# Energino.net
KiCad netlist of a schematic drawn in Altium Designer
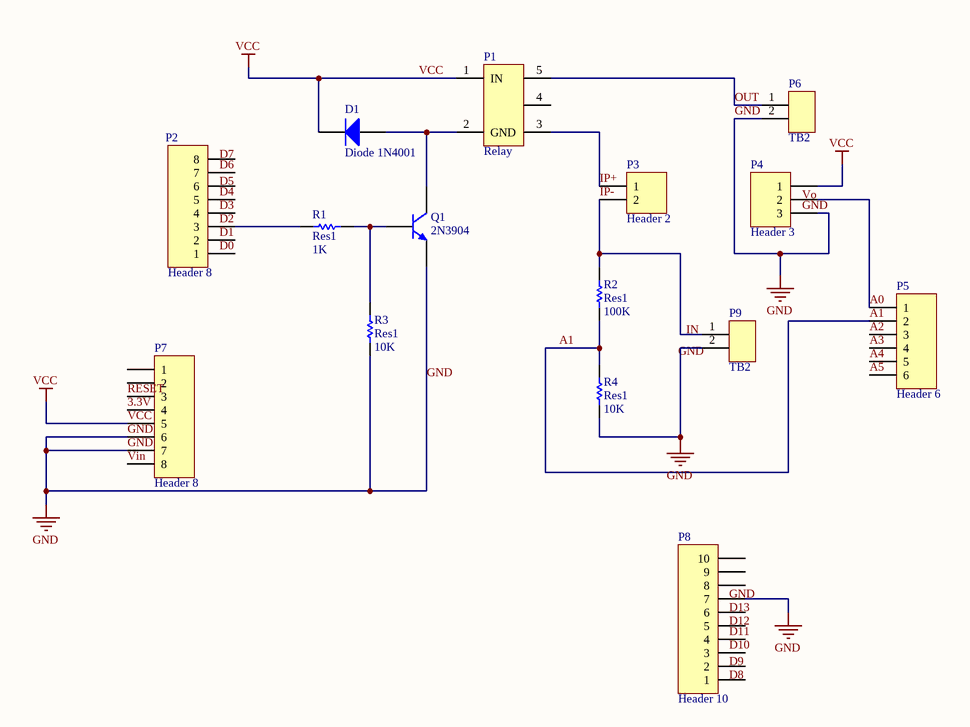
[diagram p0: Energino.SchDoc]

(export (version "E")
  (design (tool "Eeschema 10.0.6"))
  (components
    (comp (ref "D1")
      (value "Diode 1N4001")
      (footprint "DO-41")
      (description "1 Amp General Purpose Rectifier")
      (fields (field (name "PUBLISHER") "Altium Limited"))
      (libsource (lib "Miscellaneous Devices") (part "Diode 1N4001"))
    )
    (comp (ref "P1") (value "Relay") (footprint "JQC-3F") (libsource (lib "Winton") (part "JQC-3F")))
    (comp (ref "P2")
      (value "Header 8")
      (footprint "HDR1X8")
      (description "Header, 8-Pin")
      (fields (field (name "PUBLISHER") "Altium Limited"))
      (libsource (lib "") (part "Header 8_1"))
    )
    (comp (ref "P3")
      (value "Header 2")
      (footprint "HDR1X2")
      (description "Header, 2-Pin")
      (fields (field (name "PUBLISHER") "Altium Limited"))
      (libsource (lib "Miscellaneous Connectors") (part "Header 2"))
    )
    (comp (ref "P4")
      (value "Header 3")
      (footprint "HDR1X3")
      (description "Header, 3-Pin")
      (fields (field (name "PUBLISHER") "Altium Limited"))
      (libsource (lib "Miscellaneous Connectors") (part "Header 3"))
    )
    (comp (ref "P5")
      (value "Header 6")
      (footprint "HDR1X6")
      (description "Header, 6-Pin")
      (fields (field (name "PUBLISHER") "Altium Limited"))
      (libsource (lib "Miscellaneous Connectors") (part "Header 6"))
    )
    (comp (ref "P6") (value "TB2") (footprint "TB2") (libsource (lib "Winton") (part "TB2")))
    (comp (ref "P7")
      (value "Header 8")
      (footprint "HDR1X8")
      (description "Header, 8-Pin")
      (fields (field (name "PUBLISHER") "Altium Limited"))
      (libsource (lib "Miscellaneous Connectors") (part "Header 8"))
    )
    (comp (ref "P8")
      (value "Header 10")
      (footprint "HDR1X10")
      (description "Header, 10-Pin")
      (fields (field (name "PUBLISHER") "Altium Limited"))
      (libsource (lib "Miscellaneous Connectors") (part "Header 10"))
    )
    (comp (ref "P9") (value "TB2") (footprint "TB2") (libsource (lib "Winton") (part "TB2")))
    (comp (ref "Q1")
      (value "2N3904")
      (footprint "TO-92A")
      (description "NPN General Purpose Amplifier")
      (fields (field (name "PUBLISHER") "Altium Limited"))
      (libsource (lib "Miscellaneous Devices") (part "2N3904"))
    )
    (comp (ref "R1")
      (value "Res1")
      (footprint "AXIAL-0.3")
      (description "Resistor")
      (fields (field (name "ALTIUM_VALUE") "1K") (field (name "PUBLISHER") "Altium Limited"))
      (libsource (lib "Miscellaneous Devices") (part "Res1"))
    )
    (comp (ref "R2")
      (value "Res1")
      (footprint "AXIAL-0.3")
      (description "Resistor")
      (fields (field (name "ALTIUM_VALUE") "100K") (field (name "PUBLISHER") "Altium Limited"))
      (libsource (lib "Miscellaneous Devices") (part "Res1"))
    )
    (comp (ref "R3")
      (value "Res1")
      (footprint "AXIAL-0.3")
      (description "Resistor")
      (fields (field (name "ALTIUM_VALUE") "10K") (field (name "PUBLISHER") "Altium Limited"))
      (libsource (lib "Miscellaneous Devices") (part "Res1"))
    )
    (comp (ref "R4")
      (value "Res1")
      (footprint "AXIAL-0.3")
      (description "Resistor")
      (fields (field (name "ALTIUM_VALUE") "10K") (field (name "PUBLISHER") "Altium Limited"))
      (libsource (lib "Miscellaneous Devices") (part "Res1"))
    )
  )
  (nets
    (net (code "1") (name "/3.3V") (class "Default")
      (node (ref "P7") (pin "4") (pinfunction "4_4") (pintype "passive"))
    )
    (net (code "2") (name "/A0") (class "Default")
      (node (ref "P4") (pin "2") (pinfunction "2_2") (pintype "passive"))
      (node (ref "P5") (pin "1") (pinfunction "1_1") (pintype "passive"))
    )
    (net (code "3") (name "/A1") (class "Default")
      (node (ref "P5") (pin "2") (pinfunction "2_2") (pintype "passive"))
      (node (ref "R2") (pin "1") (pinfunction "1_1") (pintype "passive"))
      (node (ref "R4") (pin "2") (pinfunction "2_2") (pintype "passive"))
    )
    (net (code "4") (name "/A2") (class "Default")
      (node (ref "P5") (pin "3") (pinfunction "3_3") (pintype "passive"))
    )
    (net (code "5") (name "/A3") (class "Default")
      (node (ref "P5") (pin "4") (pinfunction "4_4") (pintype "passive"))
    )
    (net (code "6") (name "/A4") (class "Default")
      (node (ref "P5") (pin "5") (pinfunction "5_5") (pintype "passive"))
    )
    (net (code "7") (name "/A5") (class "Default")
      (node (ref "P5") (pin "6") (pinfunction "6_6") (pintype "passive"))
    )
    (net (code "23") (name "/IP+") (class "Default")
      (node (ref "P1") (pin "3") (pinfunction "3_3") (pintype "passive"))
      (node (ref "P3") (pin "1") (pinfunction "1_1") (pintype "passive"))
    )
    (net (code "24") (name "/IP-") (class "Default")
      (node (ref "P3") (pin "2") (pinfunction "2_2") (pintype "passive"))
      (node (ref "P9") (pin "1") (pinfunction "1_1") (pintype "passive"))
      (node (ref "R2") (pin "2") (pinfunction "2_2") (pintype "passive"))
    )
    (net (code "25") (name "/OUT") (class "Default")
      (node (ref "P1") (pin "5") (pinfunction "5_5") (pintype "passive"))
      (node (ref "P6") (pin "1") (pinfunction "1_1") (pintype "passive"))
    )
    (net (code "26") (name "/RESET") (class "Default")
      (node (ref "P7") (pin "3") (pinfunction "3_3") (pintype "passive"))
    )
    (net (code "27") (name "/Vin") (class "Default")
      (node (ref "P7") (pin "8") (pinfunction "8_8") (pintype "passive"))
    )
    (net (code "29") (name "GND") (class "Default")
      (node (ref "P4") (pin "3") (pinfunction "3_3") (pintype "passive"))
      (node (ref "P6") (pin "2") (pinfunction "2_2") (pintype "passive"))
      (node (ref "P7") (pin "6") (pinfunction "6_6") (pintype "passive"))
      (node (ref "P7") (pin "7") (pinfunction "7_7") (pintype "passive"))
      (node (ref "P8") (pin "7") (pinfunction "7_7") (pintype "passive"))
      (node (ref "P9") (pin "2") (pinfunction "2_2") (pintype "passive"))
      (node (ref "Q1") (pin "1") (pinfunction "E_1") (pintype "passive"))
      (node (ref "R3") (pin "1") (pinfunction "1_1") (pintype "passive"))
      (node (ref "R4") (pin "1") (pinfunction "1_1") (pintype "passive"))
    )
    (net (code "30") (name "Net-(D1-A)") (class "Default")
      (node (ref "D1") (pin "1") (pinfunction "A_1") (pintype "passive"))
      (node (ref "P1") (pin "2") (pinfunction "GND_2") (pintype "passive"))
      (node (ref "Q1") (pin "3") (pinfunction "C_3") (pintype "passive"))
    )
    (net (code "31") (name "Net-(P2-Pad3)") (class "Default")
      (node (ref "P2") (pin "3") (pinfunction "3_3") (pintype "passive"))
      (node (ref "R1") (pin "1") (pinfunction "1_1") (pintype "passive"))
    )
    (net (code "32") (name "Net-(Q1-B)") (class "Default")
      (node (ref "Q1") (pin "2") (pinfunction "B_2") (pintype "passive"))
      (node (ref "R1") (pin "2") (pinfunction "2_2") (pintype "passive"))
      (node (ref "R3") (pin "2") (pinfunction "2_2") (pintype "passive"))
    )
    (net (code "33") (name "VCC") (class "Default")
      (node (ref "D1") (pin "2") (pinfunction "K_2") (pintype "passive"))
      (node (ref "P1") (pin "1") (pinfunction "IN_1") (pintype "passive"))
      (node (ref "P4") (pin "1") (pinfunction "1_1") (pintype "passive"))
      (node (ref "P7") (pin "5") (pinfunction "5_5") (pintype "passive"))
    )
    (net (code "34") (name "unconnected-(P1-Pad4)") (class "Default")
      (node (ref "P1") (pin "4") (pinfunction "4_4") (pintype "passive"))
    )
    (net (code "35") (name "unconnected-(P2-Pad1)") (class "Default")
      (node (ref "P2") (pin "1") (pinfunction "1_1") (pintype "passive"))
    )
    (net (code "36") (name "unconnected-(P2-Pad2)") (class "Default")
      (node (ref "P2") (pin "2") (pinfunction "2_2") (pintype "passive"))
    )
    (net (code "37") (name "unconnected-(P2-Pad4)") (class "Default")
      (node (ref "P2") (pin "4") (pinfunction "4_4") (pintype "passive"))
    )
    (net (code "38") (name "unconnected-(P2-Pad5)") (class "Default")
      (node (ref "P2") (pin "5") (pinfunction "5_5") (pintype "passive"))
    )
    (net (code "39") (name "unconnected-(P2-Pad6)") (class "Default")
      (node (ref "P2") (pin "6") (pinfunction "6_6") (pintype "passive"))
    )
    (net (code "40") (name "unconnected-(P2-Pad7)") (class "Default")
      (node (ref "P2") (pin "7") (pinfunction "7_7") (pintype "passive"))
    )
    (net (code "41") (name "unconnected-(P2-Pad8)") (class "Default")
      (node (ref "P2") (pin "8") (pinfunction "8_8") (pintype "passive"))
    )
    (net (code "42") (name "unconnected-(P7-Pad1)") (class "Default")
      (node (ref "P7") (pin "1") (pinfunction "1_1") (pintype "passive"))
    )
    (net (code "43") (name "unconnected-(P7-Pad2)") (class "Default")
      (node (ref "P7") (pin "2") (pinfunction "2_2") (pintype "passive"))
    )
    (net (code "44") (name "unconnected-(P8-Pad1)") (class "Default")
      (node (ref "P8") (pin "1") (pinfunction "1_1") (pintype "passive"))
    )
    (net (code "45") (name "unconnected-(P8-Pad2)") (class "Default")
      (node (ref "P8") (pin "2") (pinfunction "2_2") (pintype "passive"))
    )
    (net (code "46") (name "unconnected-(P8-Pad3)") (class "Default")
      (node (ref "P8") (pin "3") (pinfunction "3_3") (pintype "passive"))
    )
    (net (code "47") (name "unconnected-(P8-Pad4)") (class "Default")
      (node (ref "P8") (pin "4") (pinfunction "4_4") (pintype "passive"))
    )
    (net (code "48") (name "unconnected-(P8-Pad5)") (class "Default")
      (node (ref "P8") (pin "5") (pinfunction "5_5") (pintype "passive"))
    )
    (net (code "49") (name "unconnected-(P8-Pad6)") (class "Default")
      (node (ref "P8") (pin "6") (pinfunction "6_6") (pintype "passive"))
    )
    (net (code "50") (name "unconnected-(P8-Pad8)") (class "Default")
      (node (ref "P8") (pin "8") (pinfunction "8_8") (pintype "passive"))
    )
    (net (code "51") (name "unconnected-(P8-Pad9)") (class "Default")
      (node (ref "P8") (pin "9") (pinfunction "9_9") (pintype "passive"))
    )
    (net (code "52") (name "unconnected-(P8-Pad10)") (class "Default")
      (node (ref "P8") (pin "10") (pinfunction "10_10") (pintype "passive"))
    )
  )
)
